# Netlight_ESP12F_Mk2.net
KiCad netlist of a schematic drawn in EAGLE
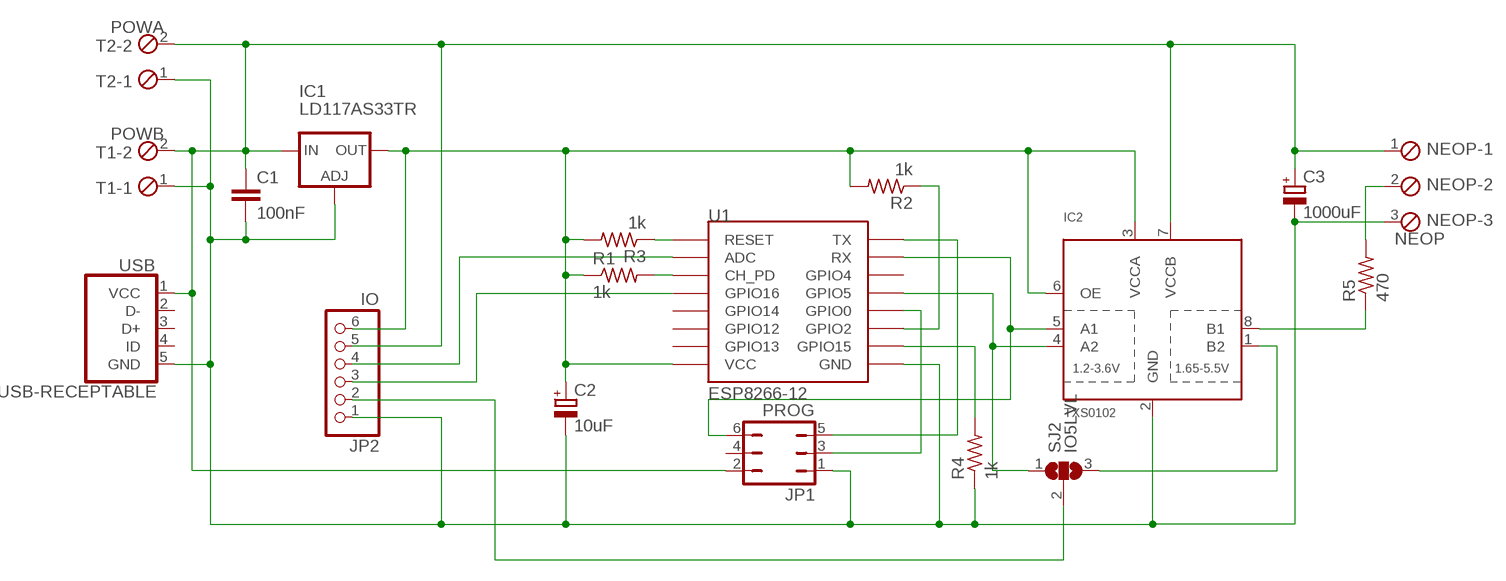
[diagram p0: schematic, sheet 1]

(export (version "E")
  (design (tool "Eeschema 10.0.6"))
  (components
    (comp (ref "C1")
      (value "100nF")
      (footprint "eagle-import:C1206")
      (libsource (lib "eagle-import") (part "C-EUC1206"))
    )
    (comp (ref "C2")
      (value "10uF")
      (footprint "eagle-import:CT3528")
      (libsource (lib "eagle-import") (part "CPOL-EUCT3528"))
    )
    (comp (ref "C3")
      (value "1000uF")
      (footprint "eagle-import:PANASONIC_G")
      (libsource (lib "eagle-import") (part "CPOL-EUG"))
    )
    (comp (ref "IC1")
      (value "LD117AS33TR")
      (footprint "eagle-import:SOT223")
      (libsource (lib "eagle-import") (part "LD117A?S33TR"))
    )
    (comp (ref "IC2")
      (value "TXS0102")
      (footprint "eagle-import:TI-SM8")
      (libsource (lib "eagle-import") (part "TXS0102SM8"))
    )
    (comp (ref "JP1")
      (value "PROG")
      (footprint "eagle-import:JP3Q")
      (libsource (lib "eagle-import") (part "JP3Q"))
    )
    (comp (ref "JP2")
      (value "IO")
      (footprint "eagle-import:1X06")
      (libsource (lib "eagle-import") (part "PINHD-1X6"))
    )
    (comp (ref "NEOP")
      (value "NEOP")
      (footprint "eagle-import:3POL254")
      (libsource (lib "eagle-import") (part "MPT3"))
    )
    (comp (ref "R1")
      (value "1k")
      (footprint "eagle-import:R0805")
      (libsource (lib "eagle-import") (part "R-US_R0805"))
    )
    (comp (ref "R2")
      (value "1k")
      (footprint "eagle-import:R0805")
      (libsource (lib "eagle-import") (part "R-US_R0805"))
    )
    (comp (ref "R3")
      (value "1k")
      (footprint "eagle-import:R0805")
      (libsource (lib "eagle-import") (part "R-US_R0805"))
    )
    (comp (ref "R4")
      (value "1k")
      (footprint "eagle-import:R0805")
      (libsource (lib "eagle-import") (part "R-US_R0805"))
    )
    (comp (ref "R5")
      (value "470")
      (footprint "eagle-import:R0805")
      (libsource (lib "eagle-import") (part "R-US_R0805"))
    )
    (comp (ref "SJ2")
      (value "IO5LVL")
      (footprint "eagle-import:SJ_2")
      (libsource (lib "eagle-import") (part "SJ2W"))
    )
    (comp (ref "T1")
      (value "POWB")
      (footprint "eagle-import:2POL254")
      (libsource (lib "eagle-import") (part "MPT2"))
    )
    (comp (ref "T2")
      (value "POWA")
      (footprint "eagle-import:2POL254")
      (libsource (lib "eagle-import") (part "MPT2"))
    )
    (comp (ref "U1")
      (value "ESP8266-12")
      (footprint "eagle-import:ESP12-SMD")
      (libsource (lib "eagle-import") (part "ESP12SMD"))
    )
    (comp (ref "USB")
      (value "USB-RECEPTABLE")
      (footprint "eagle-import:FCI-10103594-0001LF")
      (libsource (lib "eagle-import") (part "USB-RECEPTABLE"))
    )
  )
  (nets
    (net (code "1") (name "Net-(IC1-ADJ)") (class "Default")
      (node (ref "C1") (pin "2") (pinfunction "2_2") (pintype "passive"))
      (node (ref "C2") (pin "-") (pinfunction "-_-") (pintype "passive"))
      (node (ref "C3") (pin "-") (pinfunction "-_-") (pintype "passive"))
      (node (ref "IC1") (pin "1") (pinfunction "ADJ_1") (pintype "input"))
      (node (ref "IC2") (pin "2") (pinfunction "GND_2") (pintype "bidirectional"))
      (node (ref "JP1") (pin "1") (pinfunction "1_1") (pintype "passive"))
      (node (ref "JP2") (pin "1") (pinfunction "1_1") (pintype "passive"))
      (node (ref "NEOP") (pin "3") (pinfunction "1_3") (pintype "passive"))
      (node (ref "R4") (pin "1") (pinfunction "1_1") (pintype "passive"))
      (node (ref "T1") (pin "1") (pinfunction "1_1") (pintype "passive"))
      (node (ref "T2") (pin "1") (pinfunction "1_1") (pintype "passive"))
      (node (ref "U1") (pin "GND") (pinfunction "GND_GND") (pintype "bidirectional"))
      (node (ref "USB") (pin "5") (pinfunction "GND_5") (pintype "bidirectional"))
    )
    (net (code "2") (name "Net-(IC1-IN)") (class "Default")
      (node (ref "C1") (pin "1") (pinfunction "1_1") (pintype "passive"))
      (node (ref "C3") (pin "+") (pinfunction "+_+") (pintype "passive"))
      (node (ref "IC1") (pin "3") (pinfunction "IN_3") (pintype "input"))
      (node (ref "IC2") (pin "7") (pinfunction "VCCB_7") (pintype "bidirectional"))
      (node (ref "JP1") (pin "2") (pinfunction "2_2") (pintype "passive"))
      (node (ref "JP2") (pin "5") (pinfunction "5_5") (pintype "passive"))
      (node (ref "NEOP") (pin "1") (pinfunction "1_1") (pintype "passive"))
      (node (ref "T1") (pin "2") (pinfunction "1_2") (pintype "passive"))
      (node (ref "T2") (pin "2") (pinfunction "1_2") (pintype "passive"))
      (node (ref "USB") (pin "1") (pinfunction "VCC_1") (pintype "bidirectional"))
    )
    (net (code "3") (name "Net-(IC1-OUT)") (class "Default")
      (node (ref "C2") (pin "+") (pinfunction "+_+") (pintype "passive"))
      (node (ref "IC1") (pin "4") (pinfunction "OUT_4") (pintype "passive"))
      (node (ref "IC2") (pin "3") (pinfunction "VCCA_3") (pintype "bidirectional"))
      (node (ref "IC2") (pin "6") (pinfunction "OE_6") (pintype "bidirectional"))
      (node (ref "JP2") (pin "6") (pinfunction "6_6") (pintype "passive"))
      (node (ref "R1") (pin "1") (pinfunction "1_1") (pintype "passive"))
      (node (ref "R2") (pin "2") (pinfunction "2_2") (pintype "passive"))
      (node (ref "R3") (pin "2") (pinfunction "2_2") (pintype "passive"))
      (node (ref "U1") (pin "VCC") (pinfunction "VCC_VCC") (pintype "bidirectional"))
    )
    (net (code "4") (name "Net-(IC2-A1)") (class "Default")
      (node (ref "IC2") (pin "5") (pinfunction "A1_5") (pintype "bidirectional"))
      (node (ref "JP1") (pin "6") (pinfunction "6_6") (pintype "passive"))
      (node (ref "U1") (pin "RXD0") (pinfunction "RX_RXD0") (pintype "bidirectional"))
    )
    (net (code "5") (name "Net-(IC2-A2)") (class "Default")
      (node (ref "IC2") (pin "4") (pinfunction "A2_4") (pintype "bidirectional"))
      (node (ref "SJ2") (pin "1") (pinfunction "1_1") (pintype "passive"))
      (node (ref "U1") (pin "GPIO5") (pinfunction "GPIO5_GPIO5") (pintype "bidirectional"))
    )
    (net (code "6") (name "Net-(IC2-B1)") (class "Default")
      (node (ref "IC2") (pin "8") (pinfunction "B1_8") (pintype "bidirectional"))
      (node (ref "R5") (pin "1") (pinfunction "1_1") (pintype "passive"))
    )
    (net (code "7") (name "Net-(IC2-B2)") (class "Default")
      (node (ref "IC2") (pin "1") (pinfunction "B2_1") (pintype "bidirectional"))
      (node (ref "SJ2") (pin "3") (pinfunction "3_3") (pintype "passive"))
    )
    (net (code "8") (name "Net-(JP1-Pad3)") (class "Default")
      (node (ref "JP1") (pin "3") (pinfunction "3_3") (pintype "passive"))
      (node (ref "U1") (pin "GPIO0") (pinfunction "GPIO0_GPIO0") (pintype "bidirectional"))
    )
    (net (code "9") (name "Net-(JP2-Pad2)") (class "Default")
      (node (ref "JP2") (pin "2") (pinfunction "2_2") (pintype "passive"))
      (node (ref "SJ2") (pin "2") (pinfunction "2_2") (pintype "passive"))
    )
    (net (code "10") (name "Net-(JP2-Pad3)") (class "Default")
      (node (ref "JP2") (pin "3") (pinfunction "3_3") (pintype "passive"))
      (node (ref "U1") (pin "GPIO16") (pinfunction "GPIO16_GPIO16") (pintype "bidirectional"))
    )
    (net (code "11") (name "Net-(JP2-Pad4)") (class "Default")
      (node (ref "JP2") (pin "4") (pinfunction "4_4") (pintype "passive"))
      (node (ref "U1") (pin "ADC") (pinfunction "ADC_ADC") (pintype "bidirectional"))
    )
    (net (code "12") (name "Net-(NEOPB-1)") (class "Default")
      (node (ref "NEOP") (pin "2") (pinfunction "1_2") (pintype "passive"))
      (node (ref "R5") (pin "2") (pinfunction "2_2") (pintype "passive"))
    )
    (net (code "13") (name "Net-(R1-Pad2)") (class "Default")
      (node (ref "R1") (pin "2") (pinfunction "2_2") (pintype "passive"))
      (node (ref "U1") (pin "CH_PD") (pinfunction "CH_PD_CH_PD") (pintype "bidirectional"))
    )
    (net (code "14") (name "Net-(R2-Pad1)") (class "Default")
      (node (ref "R2") (pin "1") (pinfunction "1_1") (pintype "passive"))
      (node (ref "U1") (pin "GPIO2") (pinfunction "GPIO2_GPIO2") (pintype "bidirectional"))
    )
    (net (code "15") (name "Net-(R3-Pad1)") (class "Default")
      (node (ref "R3") (pin "1") (pinfunction "1_1") (pintype "passive"))
      (node (ref "U1") (pin "RESET") (pinfunction "RESET_RESET") (pintype "bidirectional"))
    )
    (net (code "16") (name "Net-(R4-Pad2)") (class "Default")
      (node (ref "R4") (pin "2") (pinfunction "2_2") (pintype "passive"))
      (node (ref "U1") (pin "GPIO15") (pinfunction "GPIO15_GPIO15") (pintype "bidirectional"))
    )
    (net (code "17") (name "Net-(U1-TX)") (class "Default")
      (node (ref "JP1") (pin "5") (pinfunction "5_5") (pintype "passive"))
      (node (ref "U1") (pin "TXD0") (pinfunction "TX_TXD0") (pintype "bidirectional"))
    )
    (net (code "18") (name "unconnected-(JP1-Pad4)") (class "Default")
      (node (ref "JP1") (pin "4") (pinfunction "4_4") (pintype "passive"))
    )
    (net (code "19") (name "unconnected-(U1-PadGPIO4)") (class "Default")
      (node (ref "U1") (pin "GPIO4") (pinfunction "GPIO4_GPIO4") (pintype "bidirectional"))
    )
    (net (code "20") (name "unconnected-(U1-PadGPIO12)") (class "Default")
      (node (ref "U1") (pin "GPIO12") (pinfunction "GPIO12_GPIO12") (pintype "bidirectional"))
    )
    (net (code "21") (name "unconnected-(U1-PadGPIO13)") (class "Default")
      (node (ref "U1") (pin "GPIO13") (pinfunction "GPIO13_GPIO13") (pintype "bidirectional"))
    )
    (net (code "22") (name "unconnected-(U1-PadGPIO14)") (class "Default")
      (node (ref "U1") (pin "GPIO14") (pinfunction "GPIO14_GPIO14") (pintype "bidirectional"))
    )
    (net (code "23") (name "unconnected-(USB-D+-Pad3)") (class "Default")
      (node (ref "USB") (pin "3") (pinfunction "D+_3") (pintype "bidirectional"))
    )
    (net (code "24") (name "unconnected-(USB-D--Pad2)") (class "Default")
      (node (ref "USB") (pin "2") (pinfunction "D-_2") (pintype "bidirectional"))
    )
    (net (code "25") (name "unconnected-(USB-ID-Pad4)") (class "Default")
      (node (ref "USB") (pin "4") (pinfunction "ID_4") (pintype "bidirectional"))
    )
  )
)
